# relay.net
KiCad netlist of a schematic drawn in Altium Designer
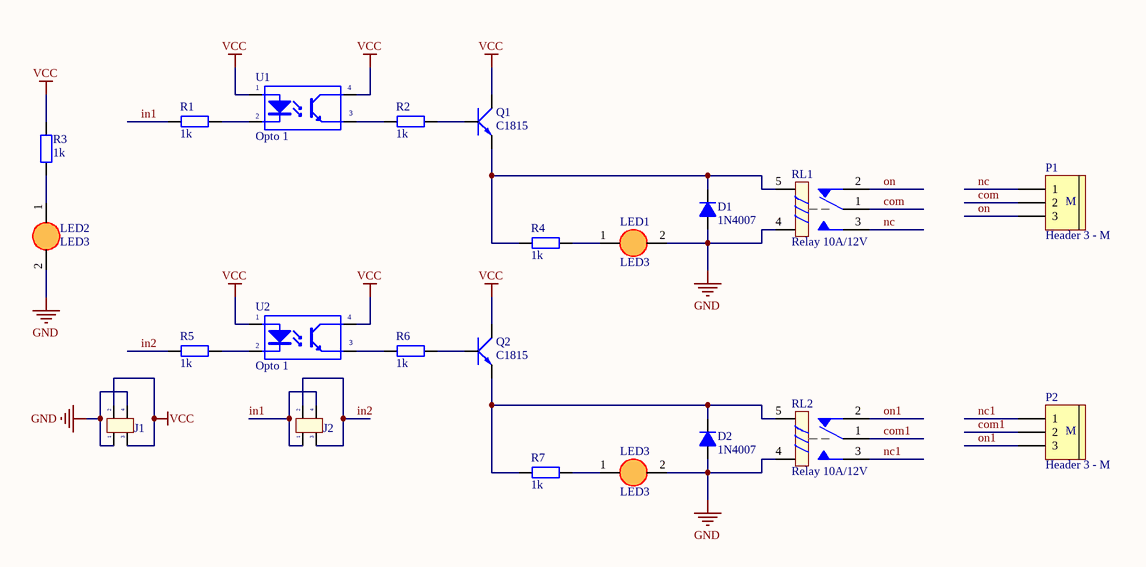
[diagram p0: relay.SchDoc]

(export (version "E")
  (design (tool "Eeschema 10.0.6"))
  (components
    (comp (ref "D1")
      (value "1N4007")
      (footprint "D1A")
      (description "Diode 1A")
      (libsource (lib "Cty1") (part "D1A"))
    )
    (comp (ref "D2")
      (value "1N4007")
      (footprint "D1A")
      (description "Diode 1A")
      (libsource (lib "Cty1") (part "D1A"))
    )
    (comp (ref "J1") (value "Jumper 2x2") (footprint "JP2X2") (libsource (lib "Cty1") (part "JP2x2")))
    (comp (ref "J2") (value "Jumper 2x2") (footprint "JP2X2") (libsource (lib "Cty1") (part "JP2x2")))
    (comp (ref "LED1")
      (value "LED3")
      (footprint "LED3mm")
      (description "LED 3mm")
      (libsource (lib "Cty1") (part "LED 3mm"))
    )
    (comp (ref "LED2")
      (value "LED3")
      (footprint "LED3mm")
      (description "LED 3mm")
      (libsource (lib "Cty1") (part "LED 3mm"))
    )
    (comp (ref "LED3")
      (value "LED3")
      (footprint "LED3mm")
      (description "LED 3mm")
      (libsource (lib "Cty1") (part "LED 3mm"))
    )
    (comp (ref "P1")
      (value "Header 3 - M")
      (footprint "Medium - Header 3")
      (description "Header, 3-Pin, Medium")
      (fields (field (name "PUBLISHER") "Altium Limited"))
      (libsource (lib "Cty1") (part "Header 3 - M"))
    )
    (comp (ref "P2")
      (value "Header 3 - M")
      (footprint "Medium - Header 3")
      (description "Header, 3-Pin, Medium")
      (fields (field (name "PUBLISHER") "Altium Limited"))
      (libsource (lib "Cty1") (part "Header 3 - M"))
    )
    (comp (ref "Q1")
      (value "C1815")
      (footprint "QTO-92")
      (description "NPN 600mW, ECB")
      (libsource (lib "Cty1") (part "C1815"))
    )
    (comp (ref "Q2")
      (value "C1815")
      (footprint "QTO-92")
      (description "NPN 600mW, ECB")
      (libsource (lib "Cty1") (part "C1815"))
    )
    (comp (ref "R1")
      (value "1k")
      (footprint "R1/4W")
      (description "Resistor 1/4W")
      (libsource (lib "Cty1") (part "R1/4W"))
    )
    (comp (ref "R2")
      (value "1k")
      (footprint "R1/4W")
      (description "Resistor 1/4W")
      (libsource (lib "Cty1") (part "R1/4W"))
    )
    (comp (ref "R3")
      (value "1k")
      (footprint "R1/4W")
      (description "Resistor 1/4W")
      (libsource (lib "Cty1") (part "R1/4W"))
    )
    (comp (ref "R4")
      (value "1k")
      (footprint "R1/4W")
      (description "Resistor 1/4W")
      (libsource (lib "Cty1") (part "R1/4W"))
    )
    (comp (ref "R5")
      (value "1k")
      (footprint "R1/4W")
      (description "Resistor 1/4W")
      (libsource (lib "Cty1") (part "R1/4W"))
    )
    (comp (ref "R6")
      (value "1k")
      (footprint "R1/4W")
      (description "Resistor 1/4W")
      (libsource (lib "Cty1") (part "R1/4W"))
    )
    (comp (ref "R7")
      (value "1k")
      (footprint "R1/4W")
      (description "Resistor 1/4W")
      (libsource (lib "Cty1") (part "R1/4W"))
    )
    (comp (ref "RL1")
      (value "Relay 10A/12V")
      (footprint "RL_SPDT_10A")
      (description "Relay SPDT,10A - 12VDC 5 Pin")
      (libsource (lib "syhaunguyen") (part "Relay 1"))
    )
    (comp (ref "RL2")
      (value "Relay 10A/12V")
      (footprint "RL_SPDT_10A")
      (description "Relay SPDT,10A - 12VDC 5 Pin")
      (libsource (lib "syhaunguyen") (part "Relay 1"))
    )
    (comp (ref "U1")
      (value "Opto 1")
      (footprint "DIP4")
      (description "Single")
      (libsource (lib "Cty1") (part "Opto 1"))
    )
    (comp (ref "U2")
      (value "Opto 1")
      (footprint "DIP4")
      (description "Single")
      (libsource (lib "Cty1") (part "Opto 1"))
    )
  )
  (nets
    (net (code "1") (name "/com") (class "Default")
      (node (ref "P1") (pin "2") (pinfunction "2_2") (pintype "passive"))
      (node (ref "RL1") (pin "1") (pinfunction "1_1") (pintype "passive"))
    )
    (net (code "2") (name "/com1") (class "Default")
      (node (ref "P2") (pin "2") (pinfunction "2_2") (pintype "passive"))
      (node (ref "RL2") (pin "1") (pinfunction "1_1") (pintype "passive"))
    )
    (net (code "3") (name "/in1") (class "Default")
      (node (ref "J2") (pin "1") (pinfunction "1_1") (pintype "passive"))
      (node (ref "J2") (pin "4") (pinfunction "4_4") (pintype "passive"))
      (node (ref "R1") (pin "1") (pinfunction "1_1") (pintype "passive"))
    )
    (net (code "4") (name "/in2") (class "Default")
      (node (ref "J2") (pin "2") (pinfunction "2_2") (pintype "passive"))
      (node (ref "J2") (pin "3") (pinfunction "3_3") (pintype "passive"))
      (node (ref "R5") (pin "1") (pinfunction "1_1") (pintype "passive"))
    )
    (net (code "5") (name "/nc") (class "Default")
      (node (ref "P1") (pin "1") (pinfunction "1_1") (pintype "passive"))
      (node (ref "RL1") (pin "3") (pinfunction "3_3") (pintype "passive"))
    )
    (net (code "6") (name "/nc1") (class "Default")
      (node (ref "P2") (pin "1") (pinfunction "1_1") (pintype "passive"))
      (node (ref "RL2") (pin "3") (pinfunction "3_3") (pintype "passive"))
    )
    (net (code "7") (name "/on") (class "Default")
      (node (ref "P1") (pin "3") (pinfunction "3_3") (pintype "passive"))
      (node (ref "RL1") (pin "2") (pinfunction "2_2") (pintype "passive"))
    )
    (net (code "8") (name "/on1") (class "Default")
      (node (ref "P2") (pin "3") (pinfunction "3_3") (pintype "passive"))
      (node (ref "RL2") (pin "2") (pinfunction "2_2") (pintype "passive"))
    )
    (net (code "9") (name "GND") (class "Default")
      (node (ref "D1") (pin "1") (pinfunction "A_1") (pintype "passive"))
      (node (ref "D2") (pin "1") (pinfunction "A_1") (pintype "passive"))
      (node (ref "J1") (pin "1") (pinfunction "1_1") (pintype "passive"))
      (node (ref "J1") (pin "4") (pinfunction "4_4") (pintype "passive"))
      (node (ref "LED1") (pin "2") (pinfunction "K_2") (pintype "passive"))
      (node (ref "LED2") (pin "2") (pinfunction "K_2") (pintype "passive"))
      (node (ref "LED3") (pin "2") (pinfunction "K_2") (pintype "passive"))
      (node (ref "RL1") (pin "4") (pinfunction "4_4") (pintype "passive"))
      (node (ref "RL2") (pin "4") (pinfunction "4_4") (pintype "passive"))
    )
    (net (code "10") (name "Net-(D1-K)") (class "Default")
      (node (ref "D1") (pin "2") (pinfunction "K_2") (pintype "passive"))
      (node (ref "Q1") (pin "1") (pinfunction "E_1") (pintype "passive"))
      (node (ref "R4") (pin "1") (pinfunction "1_1") (pintype "passive"))
      (node (ref "RL1") (pin "5") (pinfunction "5_5") (pintype "passive"))
    )
    (net (code "11") (name "Net-(D2-K)") (class "Default")
      (node (ref "D2") (pin "2") (pinfunction "K_2") (pintype "passive"))
      (node (ref "Q2") (pin "1") (pinfunction "E_1") (pintype "passive"))
      (node (ref "R7") (pin "1") (pinfunction "1_1") (pintype "passive"))
      (node (ref "RL2") (pin "5") (pinfunction "5_5") (pintype "passive"))
    )
    (net (code "12") (name "Net-(LED1-A)") (class "Default")
      (node (ref "LED1") (pin "1") (pinfunction "A_1") (pintype "passive"))
      (node (ref "R4") (pin "2") (pinfunction "2_2") (pintype "passive"))
    )
    (net (code "13") (name "Net-(LED2-A)") (class "Default")
      (node (ref "LED2") (pin "1") (pinfunction "A_1") (pintype "passive"))
      (node (ref "R3") (pin "2") (pinfunction "2_2") (pintype "passive"))
    )
    (net (code "14") (name "Net-(LED3-A)") (class "Default")
      (node (ref "LED3") (pin "1") (pinfunction "A_1") (pintype "passive"))
      (node (ref "R7") (pin "2") (pinfunction "2_2") (pintype "passive"))
    )
    (net (code "15") (name "Net-(Q1-B)") (class "Default")
      (node (ref "Q1") (pin "3") (pinfunction "B_3") (pintype "passive"))
      (node (ref "R2") (pin "2") (pinfunction "2_2") (pintype "passive"))
    )
    (net (code "16") (name "Net-(Q2-B)") (class "Default")
      (node (ref "Q2") (pin "3") (pinfunction "B_3") (pintype "passive"))
      (node (ref "R6") (pin "2") (pinfunction "2_2") (pintype "passive"))
    )
    (net (code "17") (name "Net-(U1-E)") (class "Default")
      (node (ref "R2") (pin "1") (pinfunction "1_1") (pintype "passive"))
      (node (ref "U1") (pin "3") (pinfunction "E_3") (pintype "passive"))
    )
    (net (code "18") (name "Net-(U1-K)") (class "Default")
      (node (ref "R1") (pin "2") (pinfunction "2_2") (pintype "passive"))
      (node (ref "U1") (pin "2") (pinfunction "K_2") (pintype "passive"))
    )
    (net (code "19") (name "Net-(U2-E)") (class "Default")
      (node (ref "R6") (pin "1") (pinfunction "1_1") (pintype "passive"))
      (node (ref "U2") (pin "3") (pinfunction "E_3") (pintype "passive"))
    )
    (net (code "20") (name "Net-(U2-K)") (class "Default")
      (node (ref "R5") (pin "2") (pinfunction "2_2") (pintype "passive"))
      (node (ref "U2") (pin "2") (pinfunction "K_2") (pintype "passive"))
    )
    (net (code "21") (name "VCC") (class "Default")
      (node (ref "J1") (pin "2") (pinfunction "2_2") (pintype "passive"))
      (node (ref "J1") (pin "3") (pinfunction "3_3") (pintype "passive"))
      (node (ref "Q1") (pin "2") (pinfunction "C_2") (pintype "passive"))
      (node (ref "Q2") (pin "2") (pinfunction "C_2") (pintype "passive"))
      (node (ref "R3") (pin "1") (pinfunction "1_1") (pintype "passive"))
      (node (ref "U1") (pin "1") (pinfunction "A_1") (pintype "passive"))
      (node (ref "U1") (pin "4") (pinfunction "C_4") (pintype "passive"))
      (node (ref "U2") (pin "1") (pinfunction "A_1") (pintype "passive"))
      (node (ref "U2") (pin "4") (pinfunction "C_4") (pintype "passive"))
    )
  )
)
